# arduino_isp_shield.net
KiCad netlist of a schematic drawn in EAGLE
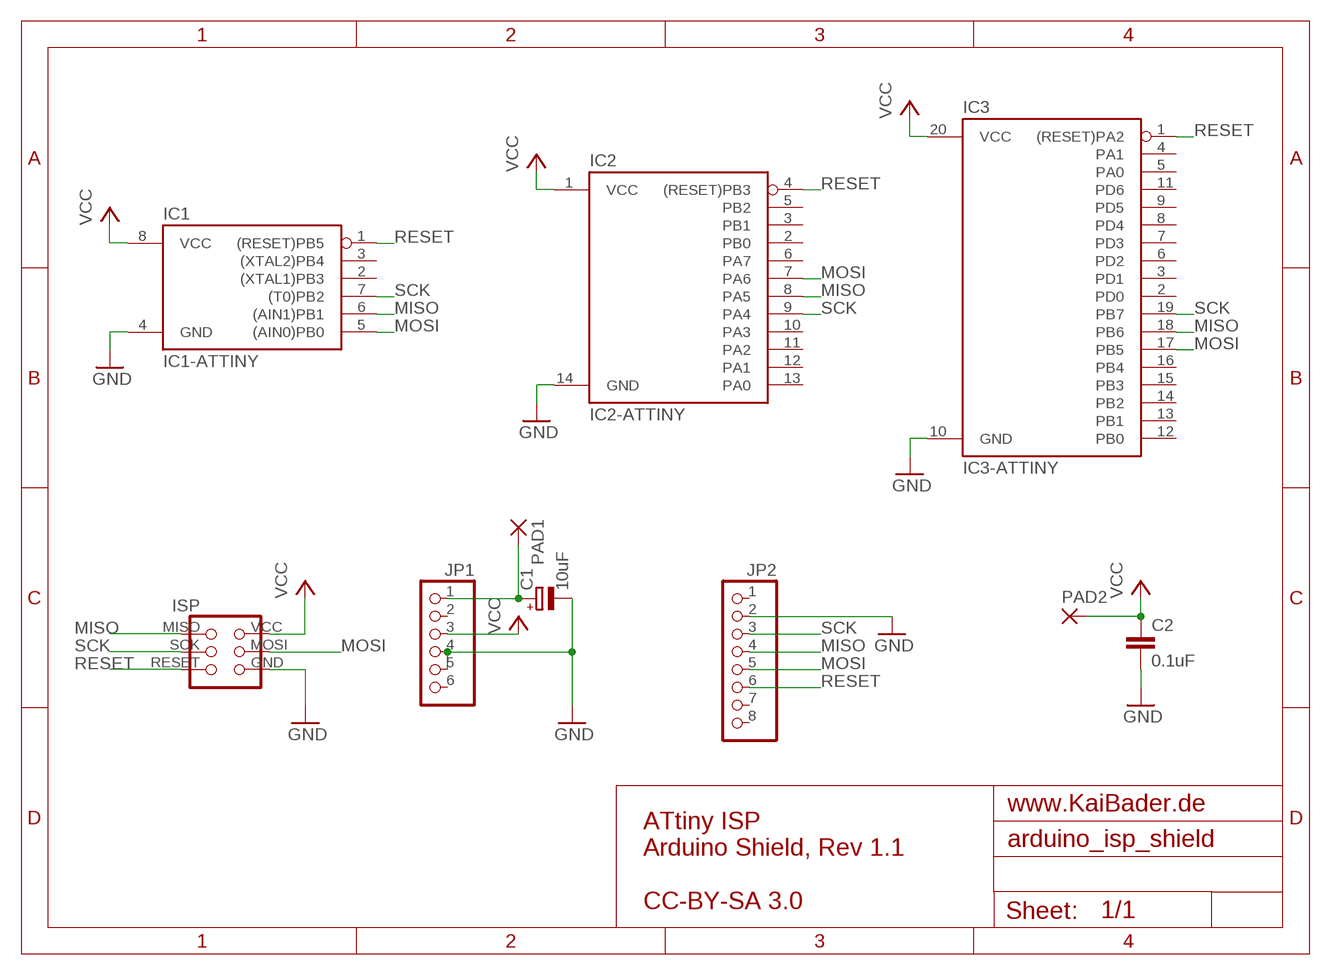
[diagram p0: schematic, sheet 1]

(export (version "E")
  (design (tool "Eeschema 10.0.6"))
  (components
    (comp (ref "C1")
      (value "10uF")
      (footprint "eagle-import:E1,8-4")
      (libsource (lib "eagle-import") (part "CPOL-EUE1.8-4"))
    )
    (comp (ref "C2")
      (value "0.1uF")
      (footprint "eagle-import:C050-025X075")
      (libsource (lib "eagle-import") (part "C-EU050-025X075"))
    )
    (comp (ref "IC1")
      (value "IC1-ATTINY")
      (footprint "eagle-import:DIL08")
      (libsource (lib "eagle-import") (part "TINY85P"))
    )
    (comp (ref "IC2")
      (value "IC2-ATTINY")
      (footprint "eagle-import:DIL14")
      (libsource (lib "eagle-import") (part "TINY84"))
    )
    (comp (ref "IC3")
      (value "IC3-ATTINY")
      (footprint "eagle-import:DIL20")
      (libsource (lib "eagle-import") (part "TINY2313"))
    )
    (comp (ref "ISP")
      (value "AVR-ISP")
      (footprint "eagle-import:AVR-ISP")
      (libsource (lib "eagle-import") (part "AVR-ISP"))
    )
    (comp (ref "JP1")
      (value "PINHD-1X6")
      (footprint "eagle-import:1X06")
      (libsource (lib "eagle-import") (part "PINHD-1X6"))
    )
    (comp (ref "JP2")
      (value "PINHD-1X8")
      (footprint "eagle-import:1X08")
      (libsource (lib "eagle-import") (part "PINHD-1X8"))
    )
    (comp (ref "PAD1")
      (value "1,6/0,8")
      (footprint "eagle-import:1,6_0,8")
      (libsource (lib "eagle-import") (part "1,6/0,8"))
    )
    (comp (ref "PAD2")
      (value "1,6/0,8")
      (footprint "eagle-import:1,6_0,8")
      (libsource (lib "eagle-import") (part "1,6/0,8"))
    )
  )
  (nets
    (net (code "1") (name "/MISO") (class "Default")
      (node (ref "IC1") (pin "6") (pinfunction "(AIN1)PB1_6") (pintype "bidirectional"))
      (node (ref "IC2") (pin "8") (pinfunction "PA5_8") (pintype "bidirectional"))
      (node (ref "IC3") (pin "18") (pinfunction "PB6_18") (pintype "bidirectional"))
      (node (ref "ISP") (pin "MISO") (pinfunction "MISO_MISO") (pintype "bidirectional"))
      (node (ref "JP2") (pin "4") (pinfunction "4_4") (pintype "passive"))
    )
    (net (code "2") (name "/MOSI") (class "Default")
      (node (ref "IC1") (pin "5") (pinfunction "(AIN0)PB0_5") (pintype "bidirectional"))
      (node (ref "IC2") (pin "7") (pinfunction "PA6_7") (pintype "bidirectional"))
      (node (ref "IC3") (pin "17") (pinfunction "PB5_17") (pintype "bidirectional"))
      (node (ref "ISP") (pin "MOSI") (pinfunction "MOSI_MOSI") (pintype "bidirectional"))
      (node (ref "JP2") (pin "5") (pinfunction "5_5") (pintype "passive"))
    )
    (net (code "3") (name "/RESET") (class "Default")
      (node (ref "IC1") (pin "1") (pinfunction "(RESET)PB5_1") (pintype "bidirectional"))
      (node (ref "IC2") (pin "4") (pinfunction "(RESET)PB3_4") (pintype "bidirectional"))
      (node (ref "IC3") (pin "1") (pinfunction "(RESET)PA2_1") (pintype "bidirectional"))
      (node (ref "ISP") (pin "RESET") (pinfunction "RESET_RESET") (pintype "bidirectional"))
      (node (ref "JP2") (pin "6") (pinfunction "6_6") (pintype "passive"))
    )
    (net (code "4") (name "/SCK") (class "Default")
      (node (ref "IC1") (pin "7") (pinfunction "(T0)PB2_7") (pintype "bidirectional"))
      (node (ref "IC2") (pin "9") (pinfunction "PA4_9") (pintype "bidirectional"))
      (node (ref "IC3") (pin "19") (pinfunction "PB7_19") (pintype "bidirectional"))
      (node (ref "ISP") (pin "SCK") (pinfunction "SCK_SCK") (pintype "bidirectional"))
      (node (ref "JP2") (pin "3") (pinfunction "3_3") (pintype "passive"))
    )
    (net (code "5") (name "GND") (class "Default")
      (node (ref "C1") (pin "-") (pinfunction "-_-") (pintype "passive"))
      (node (ref "C2") (pin "2") (pinfunction "2_2") (pintype "passive"))
      (node (ref "IC1") (pin "4") (pinfunction "GND_4") (pintype "power_in"))
      (node (ref "IC2") (pin "14") (pinfunction "GND_14") (pintype "power_in"))
      (node (ref "IC3") (pin "10") (pinfunction "GND_10") (pintype "power_in"))
      (node (ref "ISP") (pin "GND") (pinfunction "GND_GND") (pintype "power_in"))
      (node (ref "JP1") (pin "4") (pinfunction "4_4") (pintype "passive"))
      (node (ref "JP1") (pin "5") (pinfunction "5_5") (pintype "passive"))
      (node (ref "JP2") (pin "2") (pinfunction "2_2") (pintype "passive"))
    )
    (net (code "6") (name "Net-(PAD1-P)") (class "Default")
      (node (ref "C1") (pin "+") (pinfunction "+_+") (pintype "passive"))
      (node (ref "JP1") (pin "1") (pinfunction "1_1") (pintype "passive"))
      (node (ref "PAD1") (pin "1") (pinfunction "P_1") (pintype "passive"))
    )
    (net (code "7") (name "VCC") (class "Default")
      (node (ref "C2") (pin "1") (pinfunction "1_1") (pintype "passive"))
      (node (ref "IC1") (pin "8") (pinfunction "VCC_8") (pintype "power_in"))
      (node (ref "IC2") (pin "1") (pinfunction "VCC_1") (pintype "power_in"))
      (node (ref "IC3") (pin "20") (pinfunction "VCC_20") (pintype "power_in"))
      (node (ref "ISP") (pin "VCC") (pinfunction "VCC_VCC") (pintype "power_in"))
      (node (ref "JP1") (pin "3") (pinfunction "3_3") (pintype "passive"))
      (node (ref "PAD2") (pin "1") (pinfunction "P_1") (pintype "passive"))
    )
    (net (code "8") (name "unconnected-(IC1-(XTAL1)PB3-Pad2)") (class "Default")
      (node (ref "IC1") (pin "2") (pinfunction "(XTAL1)PB3_2") (pintype "bidirectional"))
    )
    (net (code "9") (name "unconnected-(IC1-(XTAL2)PB4-Pad3)") (class "Default")
      (node (ref "IC1") (pin "3") (pinfunction "(XTAL2)PB4_3") (pintype "bidirectional"))
    )
    (net (code "10") (name "unconnected-(IC2-PA0-Pad13)") (class "Default")
      (node (ref "IC2") (pin "13") (pinfunction "PA0_13") (pintype "bidirectional"))
    )
    (net (code "11") (name "unconnected-(IC2-PA1-Pad12)") (class "Default")
      (node (ref "IC2") (pin "12") (pinfunction "PA1_12") (pintype "bidirectional"))
    )
    (net (code "12") (name "unconnected-(IC2-PA2-Pad11)") (class "Default")
      (node (ref "IC2") (pin "11") (pinfunction "PA2_11") (pintype "bidirectional"))
    )
    (net (code "13") (name "unconnected-(IC2-PA3-Pad10)") (class "Default")
      (node (ref "IC2") (pin "10") (pinfunction "PA3_10") (pintype "bidirectional"))
    )
    (net (code "14") (name "unconnected-(IC2-PA7-Pad6)") (class "Default")
      (node (ref "IC2") (pin "6") (pinfunction "PA7_6") (pintype "bidirectional"))
    )
    (net (code "15") (name "unconnected-(IC2-PB0-Pad2)") (class "Default")
      (node (ref "IC2") (pin "2") (pinfunction "PB0_2") (pintype "bidirectional"))
    )
    (net (code "16") (name "unconnected-(IC2-PB1-Pad3)") (class "Default")
      (node (ref "IC2") (pin "3") (pinfunction "PB1_3") (pintype "bidirectional"))
    )
    (net (code "17") (name "unconnected-(IC2-PB2-Pad5)") (class "Default")
      (node (ref "IC2") (pin "5") (pinfunction "PB2_5") (pintype "bidirectional"))
    )
    (net (code "18") (name "unconnected-(IC3-PA0-Pad5)") (class "Default")
      (node (ref "IC3") (pin "5") (pinfunction "PA0_5") (pintype "bidirectional"))
    )
    (net (code "19") (name "unconnected-(IC3-PA1-Pad4)") (class "Default")
      (node (ref "IC3") (pin "4") (pinfunction "PA1_4") (pintype "bidirectional"))
    )
    (net (code "20") (name "unconnected-(IC3-PB0-Pad12)") (class "Default")
      (node (ref "IC3") (pin "12") (pinfunction "PB0_12") (pintype "bidirectional"))
    )
    (net (code "21") (name "unconnected-(IC3-PB1-Pad13)") (class "Default")
      (node (ref "IC3") (pin "13") (pinfunction "PB1_13") (pintype "bidirectional"))
    )
    (net (code "22") (name "unconnected-(IC3-PB2-Pad14)") (class "Default")
      (node (ref "IC3") (pin "14") (pinfunction "PB2_14") (pintype "bidirectional"))
    )
    (net (code "23") (name "unconnected-(IC3-PB3-Pad15)") (class "Default")
      (node (ref "IC3") (pin "15") (pinfunction "PB3_15") (pintype "bidirectional"))
    )
    (net (code "24") (name "unconnected-(IC3-PB4-Pad16)") (class "Default")
      (node (ref "IC3") (pin "16") (pinfunction "PB4_16") (pintype "bidirectional"))
    )
    (net (code "25") (name "unconnected-(IC3-PD0-Pad2)") (class "Default")
      (node (ref "IC3") (pin "2") (pinfunction "PD0_2") (pintype "bidirectional"))
    )
    (net (code "26") (name "unconnected-(IC3-PD1-Pad3)") (class "Default")
      (node (ref "IC3") (pin "3") (pinfunction "PD1_3") (pintype "bidirectional"))
    )
    (net (code "27") (name "unconnected-(IC3-PD2-Pad6)") (class "Default")
      (node (ref "IC3") (pin "6") (pinfunction "PD2_6") (pintype "bidirectional"))
    )
    (net (code "28") (name "unconnected-(IC3-PD3-Pad7)") (class "Default")
      (node (ref "IC3") (pin "7") (pinfunction "PD3_7") (pintype "bidirectional"))
    )
    (net (code "29") (name "unconnected-(IC3-PD4-Pad8)") (class "Default")
      (node (ref "IC3") (pin "8") (pinfunction "PD4_8") (pintype "bidirectional"))
    )
    (net (code "30") (name "unconnected-(IC3-PD5-Pad9)") (class "Default")
      (node (ref "IC3") (pin "9") (pinfunction "PD5_9") (pintype "bidirectional"))
    )
    (net (code "31") (name "unconnected-(IC3-PD6-Pad11)") (class "Default")
      (node (ref "IC3") (pin "11") (pinfunction "PD6_11") (pintype "bidirectional"))
    )
    (net (code "32") (name "unconnected-(JP1-Pad2)") (class "Default")
      (node (ref "JP1") (pin "2") (pinfunction "2_2") (pintype "passive"))
    )
    (net (code "33") (name "unconnected-(JP1-Pad6)") (class "Default")
      (node (ref "JP1") (pin "6") (pinfunction "6_6") (pintype "passive"))
    )
    (net (code "34") (name "unconnected-(JP2-Pad1)") (class "Default")
      (node (ref "JP2") (pin "1") (pinfunction "1_1") (pintype "passive"))
    )
    (net (code "35") (name "unconnected-(JP2-Pad7)") (class "Default")
      (node (ref "JP2") (pin "7") (pinfunction "7_7") (pintype "passive"))
    )
    (net (code "36") (name "unconnected-(JP2-Pad8)") (class "Default")
      (node (ref "JP2") (pin "8") (pinfunction "8_8") (pintype "passive"))
    )
  )
)
